# esquematico.net
KiCad netlist of a schematic drawn in Altium Designer
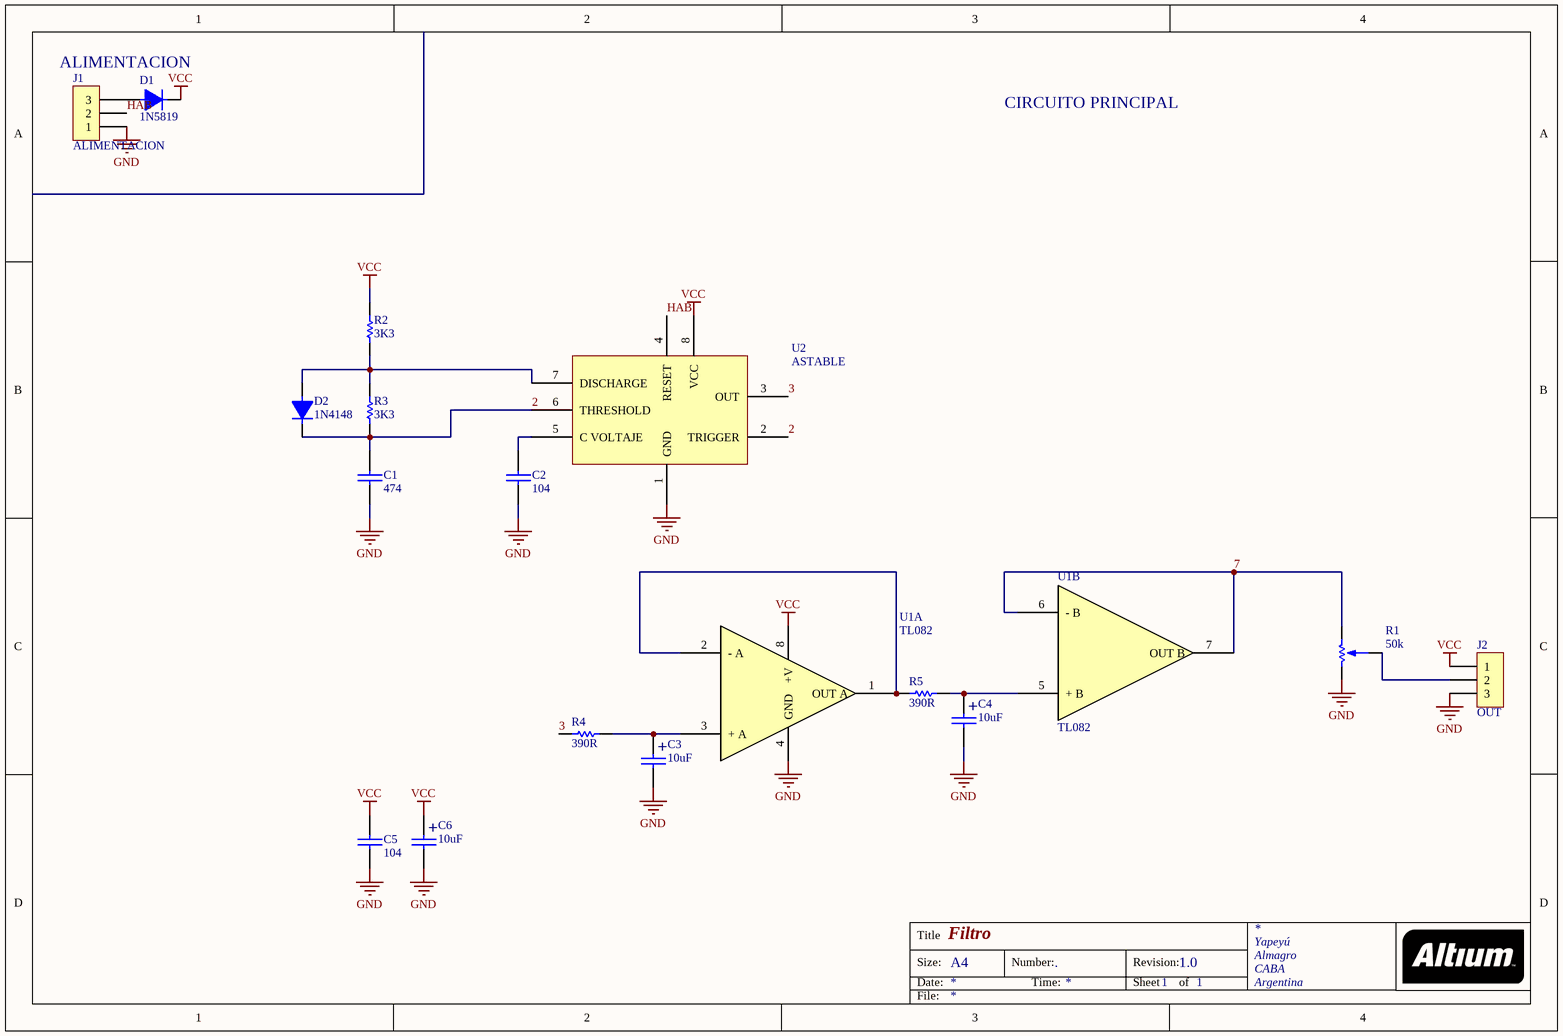
[diagram p0: esquematico.SchDoc]

(export (version "E")
  (design (tool "Eeschema 10.0.6"))
  (components
    (comp (ref "C1") (value "474") (footprint "CAP100") (libsource (lib "LIBPIOIX") (part "CAP")))
    (comp (ref "C2") (value "104") (footprint "CAP100") (libsource (lib "LIBPIOIX") (part "CAP")))
    (comp (ref "C3") (value "10uF") (footprint "CAP100RP") (libsource (lib "LIB-PIO-IX") (part "CAPPOL")))
    (comp (ref "C4") (value "10uF") (footprint "CAP100RP") (libsource (lib "LIB-PIO-IX") (part "CAPPOL")))
    (comp (ref "C5") (value "104") (footprint "CAP100") (libsource (lib "LIBPIOIX") (part "CAP")))
    (comp (ref "C6") (value "10uF") (footprint "CAP100RP") (libsource (lib "LIB-PIO-IX") (part "CAPPOL")))
    (comp (ref "D1") (value "1N5819") (footprint "DO41") (libsource (lib "LIBPIOIX") (part "DIODO")))
    (comp (ref "D2") (value "1N4148") (footprint "DO41") (libsource (lib "LIBPIOIX") (part "DIODO")))
    (comp (ref "J1") (value "ALIMENTACION") (footprint "BORNERA3") (libsource (lib "") (part "BORNERA 3_1")))
    (comp (ref "J2") (value "OUT") (footprint "BORNERA3") (libsource (lib "LIB-PIO-IX") (part "BORNERA 3")))
    (comp (ref "R1")
      (value "50k")
      (footprint "SIP3")
      (libsource (lib "Libreria Buena Onda V2") (part "POTENCIOMETRO"))
    )
    (comp (ref "R2") (value "3K3") (footprint "RES400") (libsource (lib "LIBEBAL") (part "RES")))
    (comp (ref "R3") (value "3K3") (footprint "RES400") (libsource (lib "LIBEBAL") (part "RES")))
    (comp (ref "R4") (value "390R") (footprint "RES400") (libsource (lib "LIBEBAL") (part "RES")))
    (comp (ref "R5") (value "390R") (footprint "RES400") (libsource (lib "LIBEBAL") (part "RES")))
    (comp (ref "U1")
      (value "TL082")
      (footprint "DIP8")
      (libsource (lib "Libreria Buena Onda V2") (part "TL082"))
    )
    (comp (ref "U2")
      (value "ASTABLE")
      (footprint "DIP8")
      (description "Timer")
      (libsource (lib "LIB-PIO-IX") (part "LM555"))
    )
  )
  (nets
    (net (code "1") (name "/2") (class "Default")
      (node (ref "C1") (pin "1") (pinfunction "1_1") (pintype "passive"))
      (node (ref "D2") (pin "2") (pinfunction "2_2") (pintype "passive"))
      (node (ref "R3") (pin "1") (pinfunction "1_1") (pintype "passive"))
      (node (ref "U2") (pin "2") (pinfunction "TRIGGER_2") (pintype "passive"))
      (node (ref "U2") (pin "6") (pinfunction "THRESHOLD_6") (pintype "passive"))
    )
    (net (code "2") (name "/3") (class "Default")
      (node (ref "R4") (pin "2") (pinfunction "2_2") (pintype "passive"))
      (node (ref "U2") (pin "3") (pinfunction "OUT_3") (pintype "passive"))
    )
    (net (code "3") (name "/7") (class "Default")
      (node (ref "R1") (pin "3") (pinfunction "3_3") (pintype "passive"))
      (node (ref "U1") (pin "6") (pinfunction "-_B_6") (pintype "passive"))
      (node (ref "U1") (pin "7") (pinfunction "OUT_B_7") (pintype "passive"))
    )
    (net (code "4") (name "/HAB") (class "Default")
      (node (ref "J1") (pin "2") (pinfunction "2_2") (pintype "passive"))
      (node (ref "U2") (pin "4") (pinfunction "RESET_4") (pintype "passive"))
    )
    (net (code "5") (name "GND") (class "Default")
      (node (ref "C1") (pin "2") (pinfunction "2_2") (pintype "passive"))
      (node (ref "C2") (pin "2") (pinfunction "2_2") (pintype "passive"))
      (node (ref "C3") (pin "2") (pinfunction "2_2") (pintype "passive"))
      (node (ref "C4") (pin "2") (pinfunction "2_2") (pintype "passive"))
      (node (ref "C5") (pin "2") (pinfunction "2_2") (pintype "passive"))
      (node (ref "C6") (pin "2") (pinfunction "2_2") (pintype "passive"))
      (node (ref "J1") (pin "1") (pinfunction "1_1") (pintype "passive"))
      (node (ref "J2") (pin "3") (pinfunction "3_3") (pintype "passive"))
      (node (ref "R1") (pin "1") (pinfunction "1_1") (pintype "passive"))
      (node (ref "U1") (pin "4") (pinfunction "GND_4") (pintype "passive"))
      (node (ref "U2") (pin "1") (pinfunction "GND_1") (pintype "passive"))
    )
    (net (code "6") (name "Net-(D1-Pad1)") (class "Default")
      (node (ref "D1") (pin "1") (pinfunction "1_1") (pintype "passive"))
      (node (ref "J1") (pin "3") (pinfunction "3_3") (pintype "passive"))
    )
    (net (code "7") (name "Net-(J2-Pad2)") (class "Default")
      (node (ref "J2") (pin "2") (pinfunction "2_2") (pintype "passive"))
      (node (ref "R1") (pin "2") (pinfunction "2_2") (pintype "passive"))
    )
    (net (code "8") (name "Net-(U1A-+_A)") (class "Default")
      (node (ref "C3") (pin "1") (pinfunction "1_1") (pintype "passive"))
      (node (ref "R4") (pin "1") (pinfunction "1_1") (pintype "passive"))
      (node (ref "U1") (pin "3") (pinfunction "+_A_3") (pintype "passive"))
    )
    (net (code "9") (name "Net-(U1A--_A)") (class "Default")
      (node (ref "R5") (pin "2") (pinfunction "2_2") (pintype "passive"))
      (node (ref "U1") (pin "1") (pinfunction "OUT_A_1") (pintype "passive"))
      (node (ref "U1") (pin "2") (pinfunction "-_A_2") (pintype "passive"))
    )
    (net (code "10") (name "Net-(U1B-+_B)") (class "Default")
      (node (ref "C4") (pin "1") (pinfunction "1_1") (pintype "passive"))
      (node (ref "R5") (pin "1") (pinfunction "1_1") (pintype "passive"))
      (node (ref "U1") (pin "5") (pinfunction "+_B_5") (pintype "passive"))
    )
    (net (code "11") (name "Net-(U2-C_VOLTAJE)") (class "Default")
      (node (ref "C2") (pin "1") (pinfunction "1_1") (pintype "passive"))
      (node (ref "U2") (pin "5") (pinfunction "C_VOLTAJE_5") (pintype "passive"))
    )
    (net (code "12") (name "Net-(U2-DISCHARGE)") (class "Default")
      (node (ref "D2") (pin "1") (pinfunction "1_1") (pintype "passive"))
      (node (ref "R2") (pin "1") (pinfunction "1_1") (pintype "passive"))
      (node (ref "R3") (pin "2") (pinfunction "2_2") (pintype "passive"))
      (node (ref "U2") (pin "7") (pinfunction "DISCHARGE_7") (pintype "passive"))
    )
    (net (code "13") (name "VCC") (class "Default")
      (node (ref "C5") (pin "1") (pinfunction "1_1") (pintype "passive"))
      (node (ref "C6") (pin "1") (pinfunction "1_1") (pintype "passive"))
      (node (ref "D1") (pin "2") (pinfunction "2_2") (pintype "passive"))
      (node (ref "J2") (pin "1") (pinfunction "1_1") (pintype "passive"))
      (node (ref "R2") (pin "2") (pinfunction "2_2") (pintype "passive"))
      (node (ref "U1") (pin "8") (pinfunction "+V_8") (pintype "passive"))
      (node (ref "U2") (pin "8") (pinfunction "VCC_8") (pintype "passive"))
    )
  )
)
